# Port.net
KiCad netlist of a schematic drawn in Altium Designer
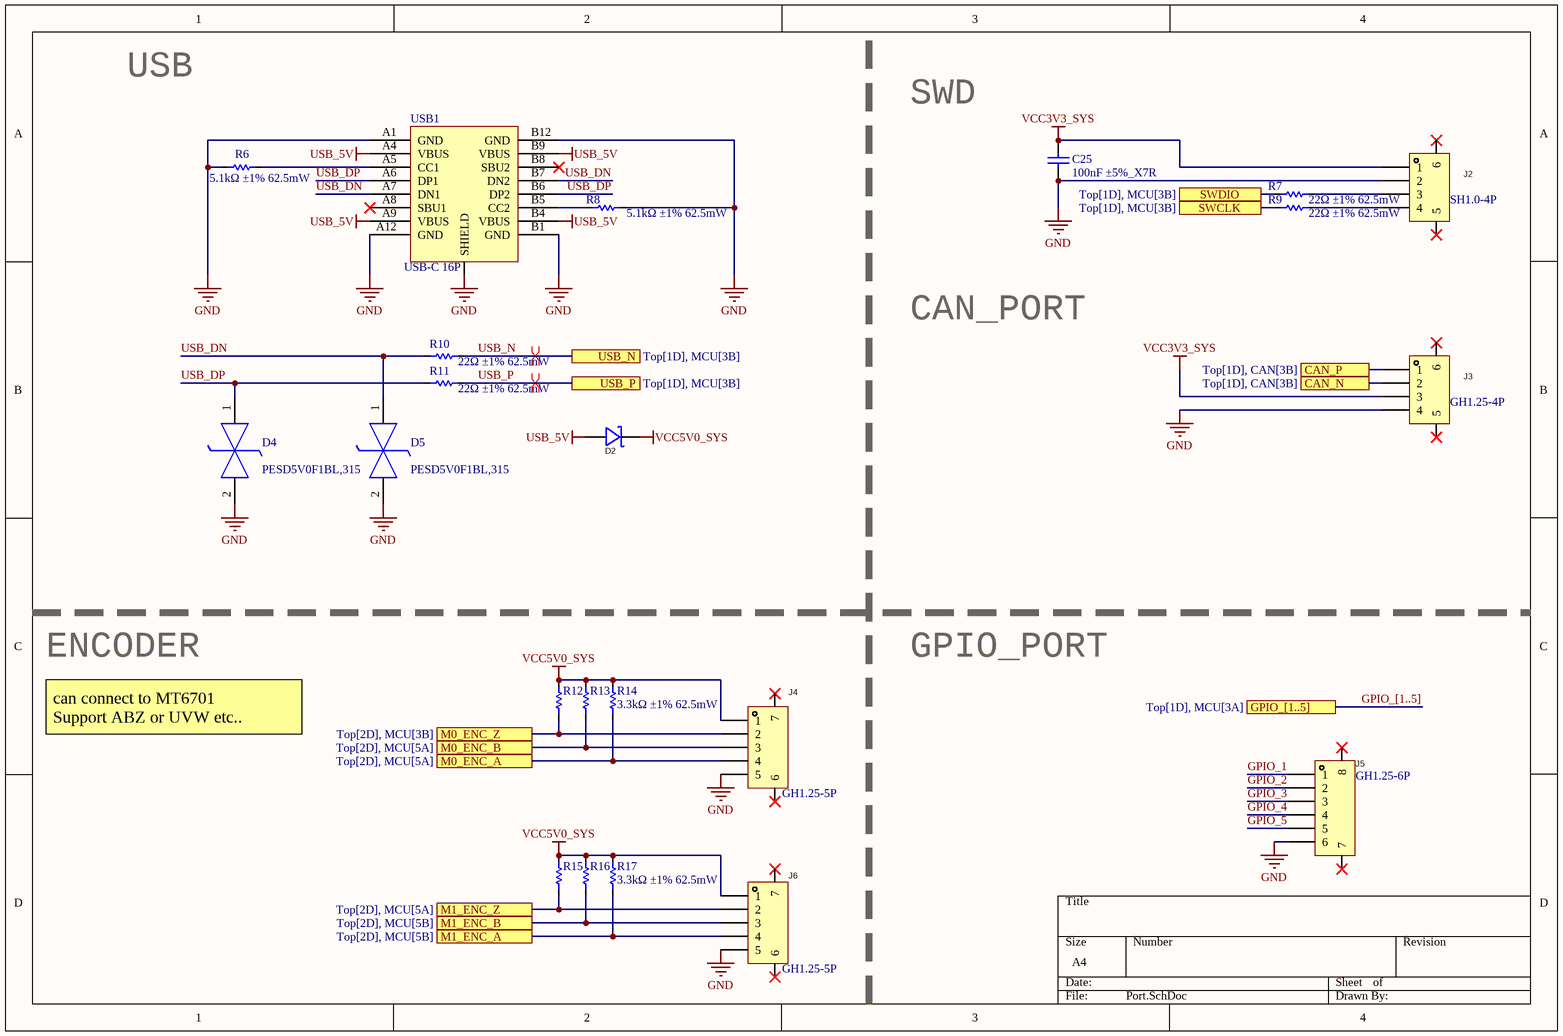
[diagram p0: Port.SchDoc]

(export (version "E")
  (design (tool "Eeschema 10.0.6"))
  (components
    (comp (ref "C25")
      (value "100nF ±5%_X7R")
      (footprint "WCAP-CSGP_0402_L1W0.5H0.5")
      (description "Capacitor")
      (fields (field (name "PUBLISHER") "Altium Limited"))
      (libsource (lib "Component") (part "Cap"))
    )
    (comp (ref "D2")
      (value "B340A-13-F")
      (footprint "SMA_L4.4-W2.6-LS5.0-RD")
      (description "直流反向耐压(Vr):40V;平均整流电流(Io):3A;正向压降(Vf):500mV@3A;")
      (fields (field (name "MANUFACTURER") "DIODES(美台)"))
      (libsource (lib "Component") (part "Diode_Schottky"))
    )
    (comp (ref "D4")
      (value "PESD5V0F1BL,315")
      (footprint "SamacSys:PESD5V0S1BL315")
      (description "Diode ESD (Bi-directional)")
      (fields (field (name "MOUSER PART NUMBER") "771-PESD5V0F1BL315"))
      (libsource (lib "*") (part "PESD5V0F1BL,315"))
    )
    (comp (ref "D5")
      (value "PESD5V0F1BL,315")
      (footprint "SamacSys:PESD5V0S1BL315")
      (description "Diode ESD (Bi-directional)")
      (fields (field (name "MOUSER PART NUMBER") "771-PESD5V0F1BL315"))
      (libsource (lib "*") (part "PESD5V0F1BL,315"))
    )
    (comp (ref "J2")
      (value "SH1.0-4P")
      (footprint "CONN-SMD_4P-P1.00_BX-SH1.0-4PWT")
      (description "CONN-SMD_4P-P1.25_532610571-2")
      (fields
        (field (name "MANUFACTURER") "BOOMELE(博穆精密)")
        (field (name "MANUFACTURER PART") "GH1.25-5PLTPZ")
      )
      (libsource (lib "Connectivity_Plugs") (part "SH1.0-4P"))
    )
    (comp (ref "J3")
      (value "GH1.25-4P")
      (footprint "GH1.25-4P")
      (fields
        (field (name "MANUFACTURER") "BOOMELE(博穆精密)")
        (field (name "MANUFACTURER PART") "GH1.25-5PLTPZ")
      )
      (libsource (lib "Connectivity_Plugs") (part "GH1.25-4P"))
    )
    (comp (ref "J4")
      (value "GH1.25-5P")
      (footprint "GH1.25-5P")
      (fields
        (field (name "MANUFACTURER") "BOOMELE(博穆精密)")
        (field (name "MANUFACTURER PART") "GH1.25-5PLTPZ")
      )
      (libsource (lib "Connectivity_Plugs") (part "GH1.25-5P"))
    )
    (comp (ref "J5")
      (value "GH1.25-6P")
      (footprint "GH1.25-6P")
      (fields
        (field (name "MANUFACTURER") "BOOMELE(博穆精密)")
        (field (name "MANUFACTURER PART") "GH1.25-5PLTPZ")
      )
      (libsource (lib "Connectivity_Plugs") (part "GH1.25-6P"))
    )
    (comp (ref "J6")
      (value "GH1.25-5P")
      (footprint "GH1.25-5P")
      (fields
        (field (name "MANUFACTURER") "BOOMELE(博穆精密)")
        (field (name "MANUFACTURER PART") "GH1.25-5PLTPZ")
      )
      (libsource (lib "Connectivity_Plugs") (part "GH1.25-5P"))
    )
    (comp (ref "R6")
      (value "5.1kΩ ±1% 62.5mW")
      (footprint "WRIS-KSKE_0402")
      (description "Resistor")
      (fields (field (name "PUBLISHER") "Altium Limited"))
      (libsource (lib "Component") (part "Res"))
    )
    (comp (ref "R7")
      (value "22Ω ±1% 62.5mW")
      (footprint "WRIS-KSKE_0402")
      (description "Resistor")
      (fields (field (name "PUBLISHER") "Altium Limited"))
      (libsource (lib "Component") (part "Res"))
    )
    (comp (ref "R8")
      (value "5.1kΩ ±1% 62.5mW")
      (footprint "WRIS-KSKE_0402")
      (description "Resistor")
      (fields (field (name "PUBLISHER") "Altium Limited"))
      (libsource (lib "Component") (part "Res"))
    )
    (comp (ref "R9")
      (value "22Ω ±1% 62.5mW")
      (footprint "WRIS-KSKE_0402")
      (description "Resistor")
      (fields (field (name "PUBLISHER") "Altium Limited"))
      (libsource (lib "Component") (part "Res"))
    )
    (comp (ref "R10")
      (value "22Ω ±1% 62.5mW")
      (footprint "WRIS-KSKE_0402")
      (description "0402WGF220JTCE")
      (fields (field (name "PUBLISHER") "Altium Limited"))
      (libsource (lib "Component") (part "Res"))
    )
    (comp (ref "R11")
      (value "22Ω ±1% 62.5mW")
      (footprint "WRIS-KSKE_0402")
      (description "0402WGF220JTCE")
      (fields (field (name "PUBLISHER") "Altium Limited"))
      (libsource (lib "Component") (part "Res"))
    )
    (comp (ref "R12")
      (value "3.3kΩ ±1% 62.5mW")
      (footprint "WRIS-KSKE_0402")
      (fields (field (name "PUBLISHER") "Altium Limited"))
      (libsource (lib "Component") (part "Res"))
    )
    (comp (ref "R13")
      (value "3.3kΩ ±1% 62.5mW")
      (footprint "WRIS-KSKE_0402")
      (fields (field (name "PUBLISHER") "Altium Limited"))
      (libsource (lib "Component") (part "Res"))
    )
    (comp (ref "R14")
      (value "3.3kΩ ±1% 62.5mW")
      (footprint "WRIS-KSKE_0402")
      (fields (field (name "PUBLISHER") "Altium Limited"))
      (libsource (lib "Component") (part "Res"))
    )
    (comp (ref "R15")
      (value "3.3kΩ ±1% 62.5mW")
      (footprint "WRIS-KSKE_0402")
      (fields (field (name "PUBLISHER") "Altium Limited"))
      (libsource (lib "Component") (part "Res"))
    )
    (comp (ref "R16")
      (value "3.3kΩ ±1% 62.5mW")
      (footprint "WRIS-KSKE_0402")
      (fields (field (name "PUBLISHER") "Altium Limited"))
      (libsource (lib "Component") (part "Res"))
    )
    (comp (ref "R17")
      (value "3.3kΩ ±1% 62.5mW")
      (footprint "WRIS-KSKE_0402")
      (fields (field (name "PUBLISHER") "Altium Limited"))
      (libsource (lib "Component") (part "Res"))
    )
    (comp (ref "USB1") (value "USB-C 16P") (footprint "USB-C-16P") (libsource (lib "USB") (part "USB-C 16P")))
  )
  (nets
    (net (code "1") (name "/CAN_N") (class "Default")
      (node (ref "J3") (pin "2") (pinfunction "2_2") (pintype "passive"))
    )
    (net (code "2") (name "/CAN_P") (class "Default")
      (node (ref "J3") (pin "1") (pinfunction "1_1") (pintype "passive"))
    )
    (net (code "3") (name "/GPIO_1") (class "Default")
      (node (ref "J5") (pin "1") (pinfunction "1_1") (pintype "passive"))
    )
    (net (code "4") (name "/GPIO_2") (class "Default")
      (node (ref "J5") (pin "2") (pinfunction "2_2") (pintype "passive"))
    )
    (net (code "5") (name "/GPIO_3") (class "Default")
      (node (ref "J5") (pin "3") (pinfunction "3_3") (pintype "passive"))
    )
    (net (code "6") (name "/GPIO_4") (class "Default")
      (node (ref "J5") (pin "4") (pinfunction "4_4") (pintype "passive"))
    )
    (net (code "7") (name "/GPIO_5") (class "Default")
      (node (ref "J5") (pin "5") (pinfunction "5_5") (pintype "passive"))
    )
    (net (code "9") (name "/M0_ENC_A") (class "Default")
      (node (ref "J4") (pin "4") (pinfunction "4_4") (pintype "passive"))
      (node (ref "R14") (pin "1") (pinfunction "1_1") (pintype "passive"))
    )
    (net (code "10") (name "/M0_ENC_B") (class "Default")
      (node (ref "J4") (pin "3") (pinfunction "3_3") (pintype "passive"))
      (node (ref "R13") (pin "1") (pinfunction "1_1") (pintype "passive"))
    )
    (net (code "11") (name "/M0_ENC_Z") (class "Default")
      (node (ref "J4") (pin "2") (pinfunction "2_2") (pintype "passive"))
      (node (ref "R12") (pin "1") (pinfunction "1_1") (pintype "passive"))
    )
    (net (code "12") (name "/M1_ENC_A") (class "Default")
      (node (ref "J6") (pin "4") (pinfunction "4_4") (pintype "passive"))
      (node (ref "R17") (pin "1") (pinfunction "1_1") (pintype "passive"))
    )
    (net (code "13") (name "/M1_ENC_B") (class "Default")
      (node (ref "J6") (pin "3") (pinfunction "3_3") (pintype "passive"))
      (node (ref "R16") (pin "1") (pinfunction "1_1") (pintype "passive"))
    )
    (net (code "14") (name "/M1_ENC_Z") (class "Default")
      (node (ref "J6") (pin "2") (pinfunction "2_2") (pintype "passive"))
      (node (ref "R15") (pin "1") (pinfunction "1_1") (pintype "passive"))
    )
    (net (code "15") (name "/SWCLK") (class "Default")
      (node (ref "R9") (pin "2") (pinfunction "2_2") (pintype "passive"))
    )
    (net (code "16") (name "/SWDIO") (class "Default")
      (node (ref "R7") (pin "1") (pinfunction "1_1") (pintype "passive"))
    )
    (net (code "17") (name "/USB_DN") (class "Default")
      (node (ref "D5") (pin "1") (pinfunction "K1_1") (pintype "passive"))
      (node (ref "R10") (pin "1") (pinfunction "1_1") (pintype "passive"))
      (node (ref "USB1") (pin "A7") (pinfunction "DN1_A7") (pintype "passive"))
      (node (ref "USB1") (pin "B7") (pinfunction "DN2_B7") (pintype "passive"))
    )
    (net (code "18") (name "/USB_DP") (class "Default")
      (node (ref "D4") (pin "1") (pinfunction "K1_1") (pintype "passive"))
      (node (ref "R11") (pin "1") (pinfunction "1_1") (pintype "passive"))
      (node (ref "USB1") (pin "A6") (pinfunction "DP1_A6") (pintype "passive"))
      (node (ref "USB1") (pin "B6") (pinfunction "DP2_B6") (pintype "passive"))
    )
    (net (code "19") (name "/USB_N") (class "Default")
      (node (ref "R10") (pin "2") (pinfunction "2_2") (pintype "passive"))
    )
    (net (code "20") (name "/USB_P") (class "Default")
      (node (ref "R11") (pin "2") (pinfunction "2_2") (pintype "passive"))
    )
    (net (code "21") (name "GND") (class "Default")
      (node (ref "C25") (pin "1") (pinfunction "1_1") (pintype "passive"))
      (node (ref "D4") (pin "2") (pinfunction "K2_2") (pintype "passive"))
      (node (ref "D5") (pin "2") (pinfunction "K2_2") (pintype "passive"))
      (node (ref "J2") (pin "2") (pinfunction "2_2") (pintype "passive"))
      (node (ref "J3") (pin "4") (pinfunction "4_4") (pintype "passive"))
      (node (ref "J4") (pin "5") (pinfunction "5_5") (pintype "passive"))
      (node (ref "J5") (pin "6") (pinfunction "6_6") (pintype "passive"))
      (node (ref "J6") (pin "5") (pinfunction "5_5") (pintype "passive"))
      (node (ref "R6") (pin "1") (pinfunction "1_1") (pintype "passive"))
      (node (ref "R8") (pin "2") (pinfunction "2_2") (pintype "passive"))
      (node (ref "USB1") (pin "0") (pinfunction "SHIELD_0") (pintype "passive"))
      (node (ref "USB1") (pin "A1") (pinfunction "GND_A1") (pintype "passive"))
      (node (ref "USB1") (pin "A12") (pinfunction "GND_A12") (pintype "passive"))
      (node (ref "USB1") (pin "B1") (pinfunction "GND_B1") (pintype "passive"))
      (node (ref "USB1") (pin "B12") (pinfunction "GND_B12") (pintype "passive"))
    )
    (net (code "22") (name "Net-(J2-Pad3)") (class "Default")
      (node (ref "J2") (pin "3") (pinfunction "3_3") (pintype "passive"))
      (node (ref "R7") (pin "2") (pinfunction "2_2") (pintype "passive"))
    )
    (net (code "23") (name "Net-(J2-Pad4)") (class "Default")
      (node (ref "J2") (pin "4") (pinfunction "4_4") (pintype "passive"))
      (node (ref "R9") (pin "1") (pinfunction "1_1") (pintype "passive"))
    )
    (net (code "24") (name "Net-(USB1-CC1)") (class "Default")
      (node (ref "R6") (pin "2") (pinfunction "2_2") (pintype "passive"))
      (node (ref "USB1") (pin "A5") (pinfunction "CC1_A5") (pintype "passive"))
    )
    (net (code "25") (name "Net-(USB1-CC2)") (class "Default")
      (node (ref "R8") (pin "1") (pinfunction "1_1") (pintype "passive"))
      (node (ref "USB1") (pin "B5") (pinfunction "CC2_B5") (pintype "passive"))
    )
    (net (code "26") (name "USB_5V") (class "Default")
      (node (ref "D2") (pin "2") (pinfunction "A_2") (pintype "passive"))
      (node (ref "USB1") (pin "A4") (pinfunction "VBUS_A4") (pintype "passive"))
      (node (ref "USB1") (pin "A9") (pinfunction "VBUS_A9") (pintype "passive"))
      (node (ref "USB1") (pin "B4") (pinfunction "VBUS_B4") (pintype "passive"))
      (node (ref "USB1") (pin "B9") (pinfunction "VBUS_B9") (pintype "passive"))
    )
    (net (code "27") (name "VCC3V3_SYS") (class "Default")
      (node (ref "C25") (pin "2") (pinfunction "2_2") (pintype "passive"))
      (node (ref "J2") (pin "1") (pinfunction "1_1") (pintype "passive"))
      (node (ref "J3") (pin "3") (pinfunction "3_3") (pintype "passive"))
    )
    (net (code "28") (name "VCC5V0_SYS") (class "Default")
      (node (ref "D2") (pin "1") (pinfunction "K_1") (pintype "passive"))
      (node (ref "J4") (pin "1") (pinfunction "1_1") (pintype "passive"))
      (node (ref "J6") (pin "1") (pinfunction "1_1") (pintype "passive"))
      (node (ref "R12") (pin "2") (pinfunction "2_2") (pintype "passive"))
      (node (ref "R13") (pin "2") (pinfunction "2_2") (pintype "passive"))
      (node (ref "R14") (pin "2") (pinfunction "2_2") (pintype "passive"))
      (node (ref "R15") (pin "2") (pinfunction "2_2") (pintype "passive"))
      (node (ref "R16") (pin "2") (pinfunction "2_2") (pintype "passive"))
      (node (ref "R17") (pin "2") (pinfunction "2_2") (pintype "passive"))
    )
    (net (code "29") (name "unconnected-(J2-Pad5)") (class "Default")
      (node (ref "J2") (pin "5") (pinfunction "5_5") (pintype "passive+no_connect"))
    )
    (net (code "30") (name "unconnected-(J2-Pad6)") (class "Default")
      (node (ref "J2") (pin "6") (pinfunction "6_6") (pintype "passive+no_connect"))
    )
    (net (code "31") (name "unconnected-(J3-Pad5)") (class "Default")
      (node (ref "J3") (pin "5") (pinfunction "5_5") (pintype "passive+no_connect"))
    )
    (net (code "32") (name "unconnected-(J3-Pad6)") (class "Default")
      (node (ref "J3") (pin "6") (pinfunction "6_6") (pintype "passive+no_connect"))
    )
    (net (code "33") (name "unconnected-(J4-Pad6)") (class "Default")
      (node (ref "J4") (pin "6") (pinfunction "6_6") (pintype "passive+no_connect"))
    )
    (net (code "34") (name "unconnected-(J4-Pad7)") (class "Default")
      (node (ref "J4") (pin "7") (pinfunction "7_7") (pintype "passive+no_connect"))
    )
    (net (code "35") (name "unconnected-(J5-Pad7)") (class "Default")
      (node (ref "J5") (pin "7") (pinfunction "7_7") (pintype "passive+no_connect"))
    )
    (net (code "36") (name "unconnected-(J5-Pad8)") (class "Default")
      (node (ref "J5") (pin "8") (pinfunction "8_8") (pintype "passive+no_connect"))
    )
    (net (code "37") (name "unconnected-(J6-Pad6)") (class "Default")
      (node (ref "J6") (pin "6") (pinfunction "6_6") (pintype "passive+no_connect"))
    )
    (net (code "38") (name "unconnected-(J6-Pad7)") (class "Default")
      (node (ref "J6") (pin "7") (pinfunction "7_7") (pintype "passive+no_connect"))
    )
    (net (code "39") (name "unconnected-(USB1-SBU1-PadA8)") (class "Default")
      (node (ref "USB1") (pin "A8") (pinfunction "SBU1_A8") (pintype "passive+no_connect"))
    )
    (net (code "40") (name "unconnected-(USB1-SBU2-PadB8)") (class "Default")
      (node (ref "USB1") (pin "B8") (pinfunction "SBU2_B8") (pintype "passive+no_connect"))
    )
  )
)
